# MEZ_ALL_IND.net
KiCad netlist of a schematic drawn in Altium Designer
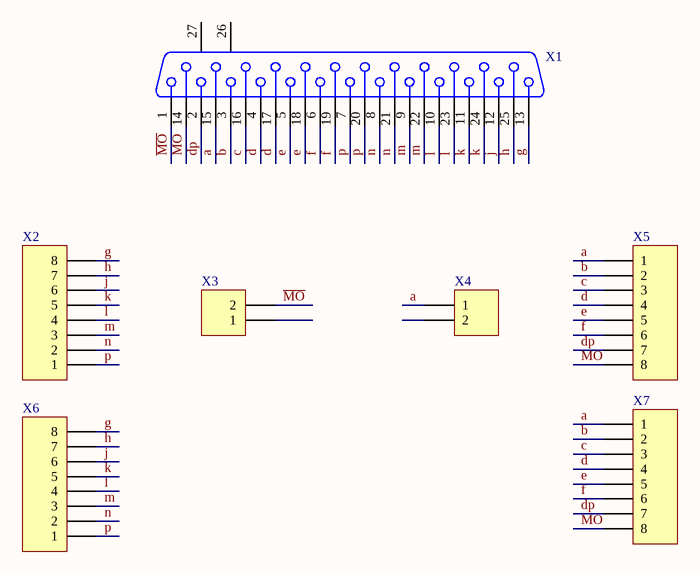
[diagram p0: MEZ_ALL_IND.SchDoc]

(export (version "E")
  (design (tool "Eeschema 10.0.6"))
  (components
    (comp (ref "X1")
      (value "D Connector 25")
      (footprint "DSUB1.385-2H25A")
      (description "Receptacle Assembly, 25 Position, Right Angle")
      (fields (field (name "PUBLISHER") "Altium Limited"))
      (libsource (lib "Miscellaneous Connectors") (part "D Connector 25"))
    )
    (comp (ref "X2")
      (value "Header 8")
      (footprint "HDR1X8")
      (description "Header, 8-Pin")
      (fields (field (name "PUBLISHER") "Altium Limited"))
      (libsource (lib "Miscellaneous Connectors") (part "Header 8"))
    )
    (comp (ref "X3")
      (value "Header 2")
      (footprint "HDR1X2")
      (description "Header, 2-Pin")
      (fields (field (name "PUBLISHER") "Altium Limited"))
      (libsource (lib "Miscellaneous Connectors") (part "Header 2"))
    )
    (comp (ref "X4")
      (value "Header 2")
      (footprint "HDR1X2")
      (description "Header, 2-Pin")
      (fields (field (name "PUBLISHER") "Altium Limited"))
      (libsource (lib "") (part "Header 2_1"))
    )
    (comp (ref "X5")
      (value "Header 8")
      (footprint "HDR1X8")
      (description "Header, 8-Pin")
      (fields (field (name "PUBLISHER") "Altium Limited"))
      (libsource (lib "") (part "Header 8_1"))
    )
    (comp (ref "X6")
      (value "Header 8")
      (footprint "HDR1X8")
      (description "Header, 8-Pin")
      (fields (field (name "PUBLISHER") "Altium Limited"))
      (libsource (lib "Miscellaneous Connectors") (part "Header 8"))
    )
    (comp (ref "X7")
      (value "Header 8")
      (footprint "HDR1X8")
      (description "Header, 8-Pin")
      (fields (field (name "PUBLISHER") "Altium Limited"))
      (libsource (lib "") (part "Header 8_1"))
    )
  )
  (nets
    (net (code "1") (name "/a") (class "Default")
      (node (ref "X1") (pin "15") (pinfunction "15_15") (pintype "passive"))
      (node (ref "X4") (pin "1") (pinfunction "1_1") (pintype "passive"))
      (node (ref "X5") (pin "1") (pinfunction "1_1") (pintype "passive"))
      (node (ref "X7") (pin "1") (pinfunction "1_1") (pintype "passive"))
    )
    (net (code "2") (name "/b") (class "Default")
      (node (ref "X1") (pin "3") (pinfunction "3_3") (pintype "passive"))
      (node (ref "X5") (pin "2") (pinfunction "2_2") (pintype "passive"))
      (node (ref "X7") (pin "2") (pinfunction "2_2") (pintype "passive"))
    )
    (net (code "3") (name "/c") (class "Default")
      (node (ref "X1") (pin "16") (pinfunction "16_16") (pintype "passive"))
      (node (ref "X5") (pin "3") (pinfunction "3_3") (pintype "passive"))
      (node (ref "X7") (pin "3") (pinfunction "3_3") (pintype "passive"))
    )
    (net (code "4") (name "/d") (class "Default")
      (node (ref "X1") (pin "17") (pinfunction "17_17") (pintype "passive"))
      (node (ref "X1") (pin "4") (pinfunction "4_4") (pintype "passive"))
      (node (ref "X5") (pin "4") (pinfunction "4_4") (pintype "passive"))
      (node (ref "X7") (pin "4") (pinfunction "4_4") (pintype "passive"))
    )
    (net (code "5") (name "/dp") (class "Default")
      (node (ref "X1") (pin "2") (pinfunction "2_2") (pintype "passive"))
      (node (ref "X5") (pin "7") (pinfunction "7_7") (pintype "passive"))
      (node (ref "X7") (pin "7") (pinfunction "7_7") (pintype "passive"))
    )
    (net (code "6") (name "/e") (class "Default")
      (node (ref "X1") (pin "18") (pinfunction "18_18") (pintype "passive"))
      (node (ref "X1") (pin "5") (pinfunction "5_5") (pintype "passive"))
      (node (ref "X5") (pin "5") (pinfunction "5_5") (pintype "passive"))
      (node (ref "X7") (pin "5") (pinfunction "5_5") (pintype "passive"))
    )
    (net (code "7") (name "/f") (class "Default")
      (node (ref "X1") (pin "19") (pinfunction "19_19") (pintype "passive"))
      (node (ref "X1") (pin "6") (pinfunction "6_6") (pintype "passive"))
      (node (ref "X5") (pin "6") (pinfunction "6_6") (pintype "passive"))
      (node (ref "X7") (pin "6") (pinfunction "6_6") (pintype "passive"))
    )
    (net (code "8") (name "/g") (class "Default")
      (node (ref "X1") (pin "13") (pinfunction "13_13") (pintype "passive"))
      (node (ref "X2") (pin "8") (pinfunction "8_8") (pintype "passive"))
      (node (ref "X6") (pin "8") (pinfunction "8_8") (pintype "passive"))
    )
    (net (code "9") (name "/h") (class "Default")
      (node (ref "X1") (pin "25") (pinfunction "25_25") (pintype "passive"))
      (node (ref "X2") (pin "7") (pinfunction "7_7") (pintype "passive"))
      (node (ref "X6") (pin "7") (pinfunction "7_7") (pintype "passive"))
    )
    (net (code "10") (name "/j") (class "Default")
      (node (ref "X1") (pin "12") (pinfunction "12_12") (pintype "passive"))
      (node (ref "X2") (pin "6") (pinfunction "6_6") (pintype "passive"))
      (node (ref "X6") (pin "6") (pinfunction "6_6") (pintype "passive"))
    )
    (net (code "11") (name "/k") (class "Default")
      (node (ref "X1") (pin "11") (pinfunction "11_11") (pintype "passive"))
      (node (ref "X1") (pin "24") (pinfunction "24_24") (pintype "passive"))
      (node (ref "X2") (pin "5") (pinfunction "5_5") (pintype "passive"))
      (node (ref "X6") (pin "5") (pinfunction "5_5") (pintype "passive"))
    )
    (net (code "12") (name "/l") (class "Default")
      (node (ref "X1") (pin "10") (pinfunction "10_10") (pintype "passive"))
      (node (ref "X1") (pin "23") (pinfunction "23_23") (pintype "passive"))
      (node (ref "X2") (pin "4") (pinfunction "4_4") (pintype "passive"))
      (node (ref "X6") (pin "4") (pinfunction "4_4") (pintype "passive"))
    )
    (net (code "13") (name "/m") (class "Default")
      (node (ref "X1") (pin "22") (pinfunction "22_22") (pintype "passive"))
      (node (ref "X1") (pin "9") (pinfunction "9_9") (pintype "passive"))
      (node (ref "X2") (pin "3") (pinfunction "3_3") (pintype "passive"))
      (node (ref "X6") (pin "3") (pinfunction "3_3") (pintype "passive"))
    )
    (net (code "14") (name "/n") (class "Default")
      (node (ref "X1") (pin "21") (pinfunction "21_21") (pintype "passive"))
      (node (ref "X1") (pin "8") (pinfunction "8_8") (pintype "passive"))
      (node (ref "X2") (pin "2") (pinfunction "2_2") (pintype "passive"))
      (node (ref "X6") (pin "2") (pinfunction "2_2") (pintype "passive"))
    )
    (net (code "15") (name "/p") (class "Default")
      (node (ref "X1") (pin "20") (pinfunction "20_20") (pintype "passive"))
      (node (ref "X1") (pin "7") (pinfunction "7_7") (pintype "passive"))
      (node (ref "X2") (pin "1") (pinfunction "1_1") (pintype "passive"))
      (node (ref "X6") (pin "1") (pinfunction "1_1") (pintype "passive"))
    )
    (net (code "16") (name "/~{MO}") (class "Default")
      (node (ref "X1") (pin "1") (pinfunction "1_1") (pintype "passive"))
      (node (ref "X1") (pin "14") (pinfunction "14_14") (pintype "passive"))
      (node (ref "X3") (pin "2") (pinfunction "2_2") (pintype "passive"))
      (node (ref "X5") (pin "8") (pinfunction "8_8") (pintype "passive"))
      (node (ref "X7") (pin "8") (pinfunction "8_8") (pintype "passive"))
    )
    (net (code "17") (name "unconnected-(X1-MH1-Pad26)") (class "Default")
      (node (ref "X1") (pin "26") (pinfunction "MH1_26") (pintype "passive"))
    )
    (net (code "18") (name "unconnected-(X1-MH2-Pad27)") (class "Default")
      (node (ref "X1") (pin "27") (pinfunction "MH2_27") (pintype "passive"))
    )
    (net (code "19") (name "unconnected-(X3-Pad1)") (class "Default")
      (node (ref "X3") (pin "1") (pinfunction "1_1") (pintype "passive"))
    )
    (net (code "20") (name "unconnected-(X4-Pad2)") (class "Default")
      (node (ref "X4") (pin "2") (pinfunction "2_2") (pintype "passive"))
    )
  )
)
